# SCH_NFC-Card-Abinisha_2024-10-10.net
KiCad netlist of a schematic drawn in EasyEDA
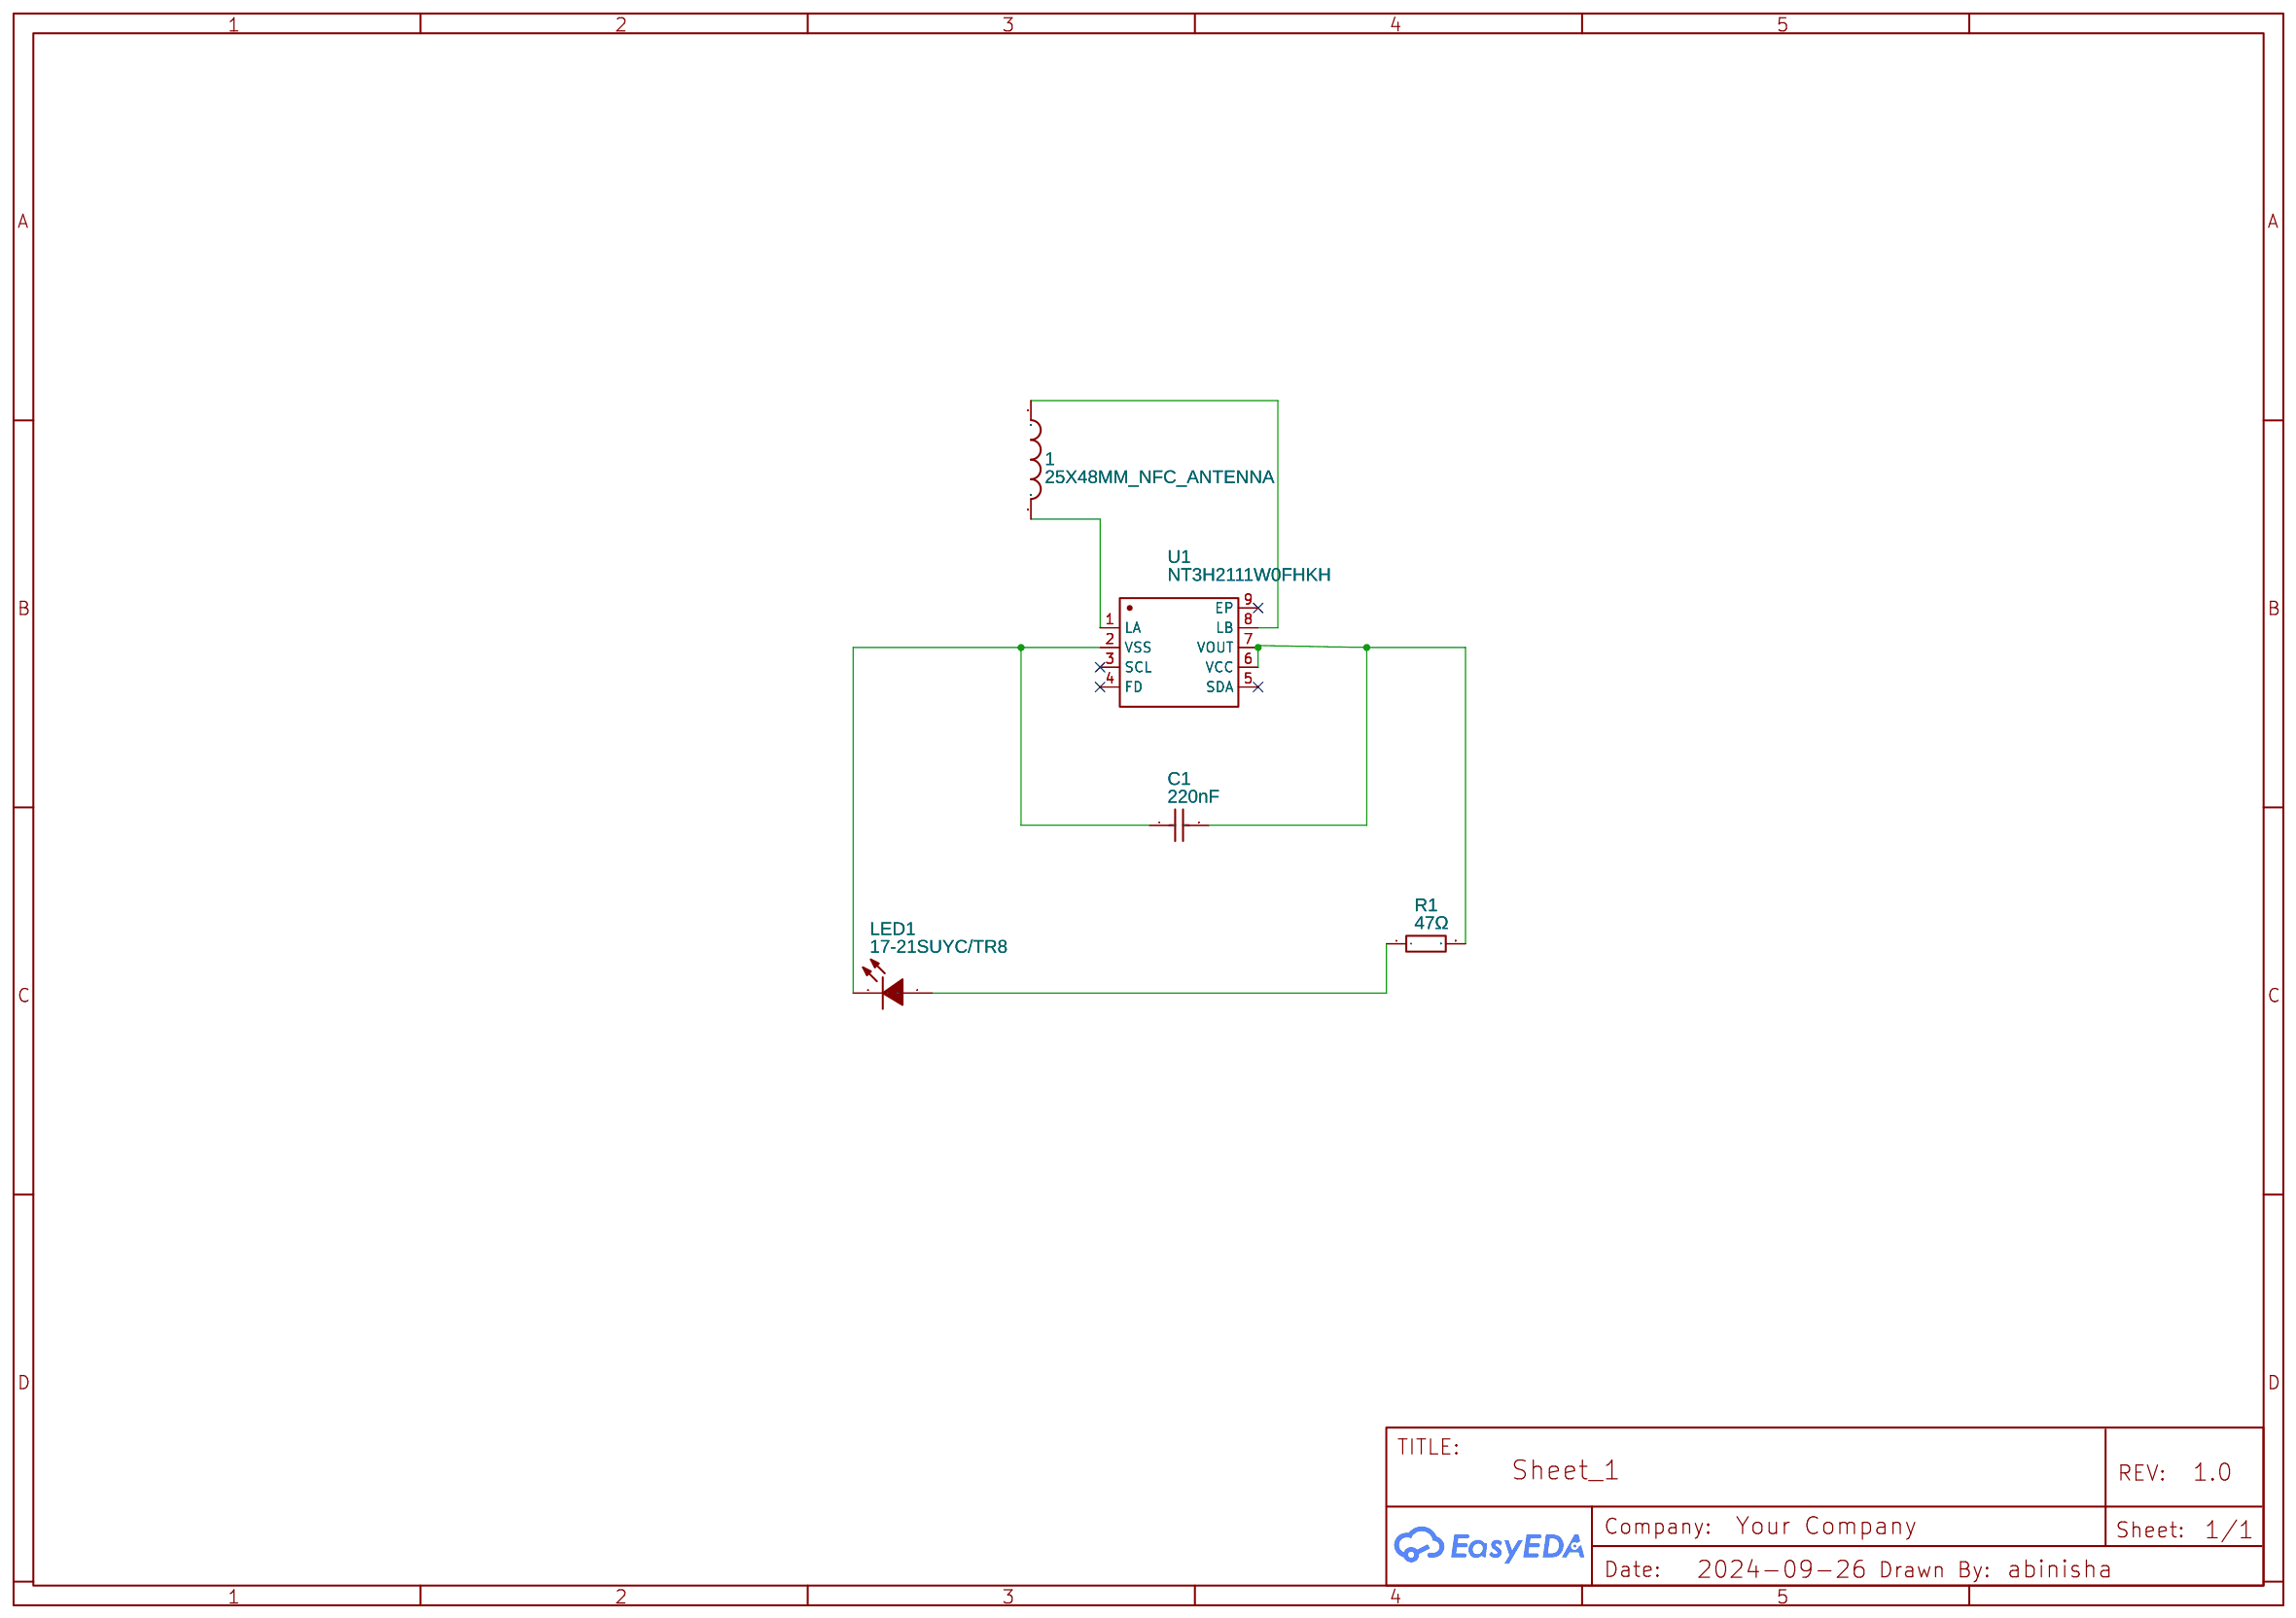
[diagram p0: schematic sheet]

(export (version "E")
  (design (tool "Eeschema 10.0.6"))
  (components
    (comp (ref "1") (value "25X48MM_NFC_ANTENNA") (libsource (lib "") (part "25X48MM_NFC_ANTENNA")))
    (comp (ref "C1")
      (value "220nF")
      (fields
        (field (name "Manufacturer Part") "CL10B224KA8NNNC")
        (field (name "Manufacturer") "SAMSUNG(三星)")
      )
      (libsource (lib "") (part "CL10B224KA8NNNC"))
    )
    (comp (ref "LED1")
      (value "17-21SUYC/TR8")
      (fields (field (name "Manufacturer Part") "KT-0805黄灯") (field (name "Manufacturer") "KENTO"))
      (libsource (lib "") (part "17-21SUYC/TR8"))
    )
    (comp (ref "R1")
      (value "47Ω")
      (fields
        (field (name "Manufacturer Part") "0603WAF470JT5E")
        (field (name "Manufacturer") "UNI-ROYAL(厚声)")
      )
      (libsource (lib "") (part "0603WAF470JT5E"))
    )
    (comp (ref "U1")
      (value "NT3H2111W0FHKH")
      (fields (field (name "Manufacturer") "NXP(恩智浦)"))
      (libsource (lib "") (part "NT3H2111W0FHKH"))
    )
  )
  (nets
    (net (code "1") (name "Net-(LED1-+)") (class "Default")
      (node (ref "LED1") (pin "1") (pinfunction "+_1") (pintype "unspecified"))
      (node (ref "R1") (pin "1") (pinfunction "1_1") (pintype "input"))
    )
    (net (code "2") (name "Net-(LED1--)") (class "Default")
      (node (ref "C1") (pin "1") (pinfunction "1_1") (pintype "input"))
      (node (ref "LED1") (pin "2") (pinfunction "-_2") (pintype "unspecified"))
      (node (ref "U1") (pin "2") (pinfunction "VSS_2") (pintype "unspecified"))
    )
    (net (code "3") (name "Net-(U1-LA)") (class "Default")
      (node (ref "1") (pin "P$2") (pinfunction "P$2_P$2") (pintype "bidirectional"))
      (node (ref "U1") (pin "1") (pinfunction "LA_1") (pintype "unspecified"))
    )
    (net (code "4") (name "Net-(U1-LB)") (class "Default")
      (node (ref "1") (pin "P$1") (pinfunction "P$1_P$1") (pintype "bidirectional"))
      (node (ref "U1") (pin "8") (pinfunction "LB_8") (pintype "unspecified"))
    )
    (net (code "5") (name "Net-(U1-VCC)") (class "Default")
      (node (ref "C1") (pin "2") (pinfunction "2_2") (pintype "input"))
      (node (ref "R1") (pin "2") (pinfunction "2_2") (pintype "input"))
      (node (ref "U1") (pin "6") (pinfunction "VCC_6") (pintype "unspecified"))
      (node (ref "U1") (pin "7") (pinfunction "VOUT_7") (pintype "unspecified"))
    )
    (net (code "6") (name "unconnected-(U1-EP-Pad9)") (class "Default")
      (node (ref "U1") (pin "9") (pinfunction "EP_9") (pintype "unspecified+no_connect"))
    )
    (net (code "7") (name "unconnected-(U1-FD-Pad4)") (class "Default")
      (node (ref "U1") (pin "4") (pinfunction "FD_4") (pintype "unspecified+no_connect"))
    )
    (net (code "8") (name "unconnected-(U1-SCL-Pad3)") (class "Default")
      (node (ref "U1") (pin "3") (pinfunction "SCL_3") (pintype "unspecified+no_connect"))
    )
    (net (code "9") (name "unconnected-(U1-SDA-Pad5)") (class "Default")
      (node (ref "U1") (pin "5") (pinfunction "SDA_5") (pintype "unspecified+no_connect"))
    )
  )
)
